# 07_-_OUTPUT.net
KiCad netlist of a schematic drawn in Altium Designer
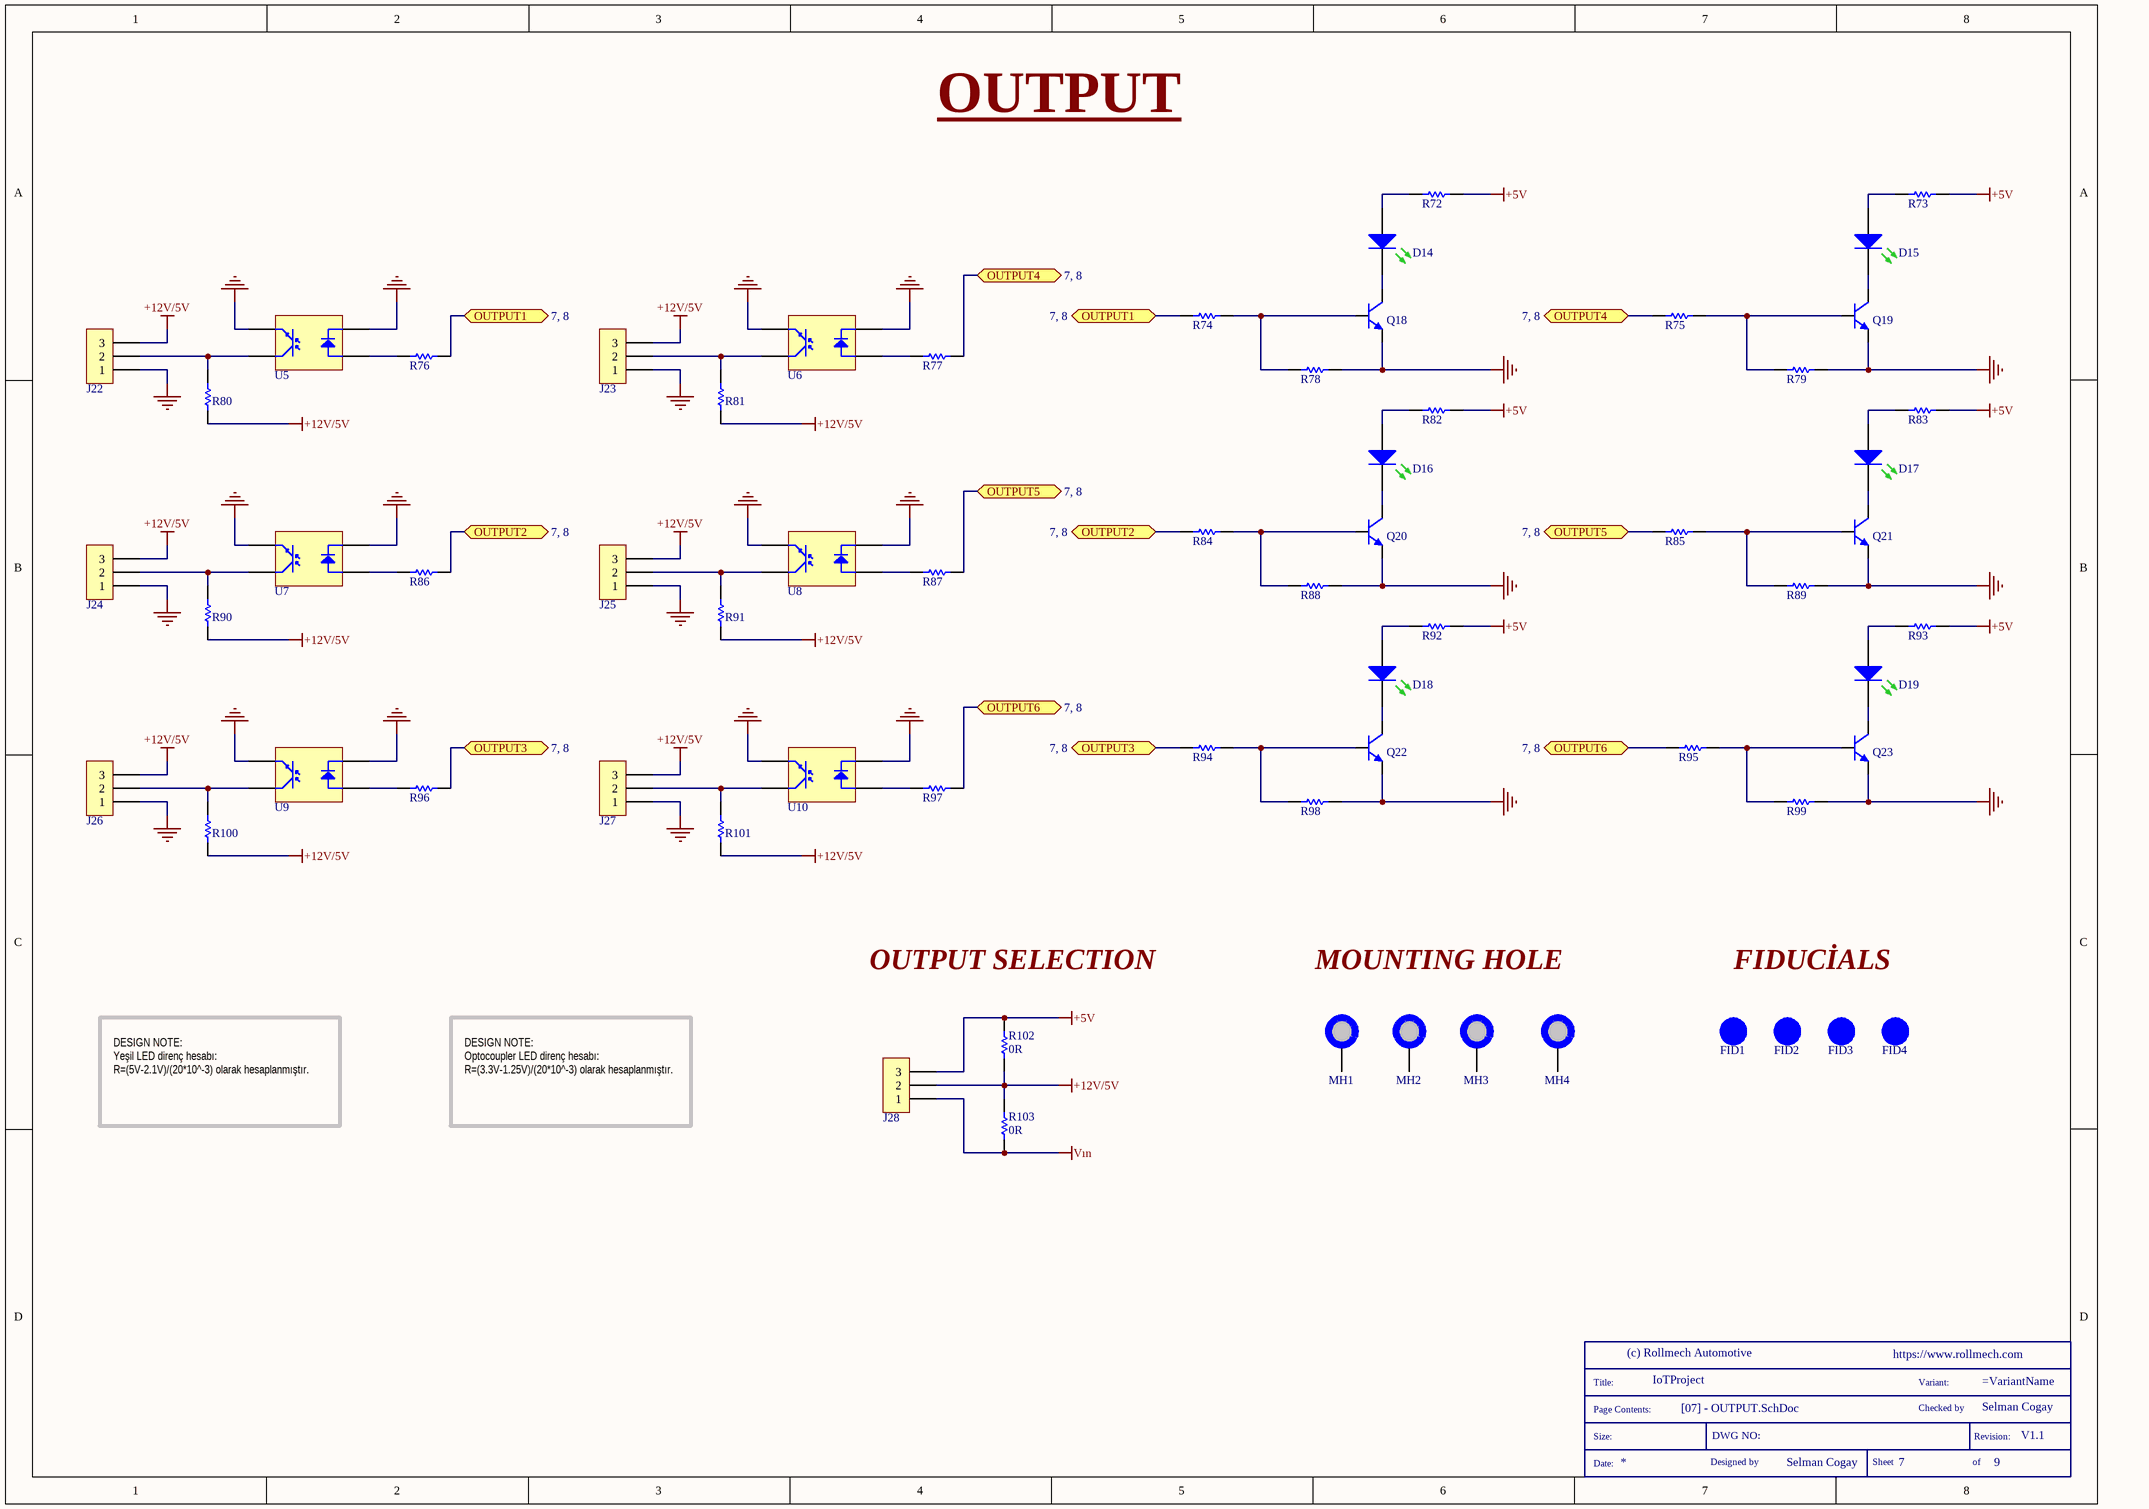
[diagram p0: [07] - OUTPUT.SchDoc]

(export (version "E")
  (design (tool "Eeschema 10.0.6"))
  (components
    (comp (ref "D14")
      (value "LED GREEN")
      (footprint "PLCC2")
      (description "LED TOPLED GREEN 562NM 2PLCC")
      (libsource (lib "Rollmech_Altium") (part "LP T67F-P1R2-35-1-20-R18-Z"))
    )
    (comp (ref "D15")
      (value "LED GREEN")
      (footprint "PLCC2")
      (description "LED TOPLED GREEN 562NM 2PLCC")
      (libsource (lib "Rollmech_Altium") (part "LP T67F-P1R2-35-1-20-R18-Z"))
    )
    (comp (ref "D16")
      (value "LED GREEN")
      (footprint "PLCC2")
      (description "LED TOPLED GREEN 562NM 2PLCC")
      (libsource (lib "Rollmech_Altium") (part "LP T67F-P1R2-35-1-20-R18-Z"))
    )
    (comp (ref "D17")
      (value "LED GREEN")
      (footprint "PLCC2")
      (description "LED TOPLED GREEN 562NM 2PLCC")
      (libsource (lib "Rollmech_Altium") (part "LP T67F-P1R2-35-1-20-R18-Z"))
    )
    (comp (ref "D18")
      (value "LED GREEN")
      (footprint "PLCC2")
      (description "LED TOPLED GREEN 562NM 2PLCC")
      (libsource (lib "Rollmech_Altium") (part "LP T67F-P1R2-35-1-20-R18-Z"))
    )
    (comp (ref "D19")
      (value "LED GREEN")
      (footprint "PLCC2")
      (description "LED TOPLED GREEN 562NM 2PLCC")
      (libsource (lib "Rollmech_Altium") (part "LP T67F-P1R2-35-1-20-R18-Z"))
    )
    (comp (ref "FID1")
      (value "FID_1MMC")
      (footprint "FID_40x120D")
      (description "Fiducial 40 mil diameter , 120 mil mask")
      (libsource (lib "Rollmech_Altium") (part "FID_1MMC"))
    )
    (comp (ref "FID2")
      (value "FID_1MMC")
      (footprint "FID_40x120D")
      (description "Fiducial 40 mil diameter , 120 mil mask")
      (libsource (lib "Rollmech_Altium") (part "FID_1MMC"))
    )
    (comp (ref "FID3")
      (value "FID_1MMC")
      (footprint "FID_40x120D")
      (description "Fiducial 40 mil diameter , 120 mil mask")
      (libsource (lib "Rollmech_Altium") (part "FID_1MMC"))
    )
    (comp (ref "FID4")
      (value "FID_1MMC")
      (footprint "FID_40x120D")
      (description "Fiducial 40 mil diameter , 120 mil mask")
      (libsource (lib "Rollmech_Altium") (part "FID_1MMC"))
    )
    (comp (ref "J22")
      (value "CONN 1X3 3MM")
      (footprint "CONN_MALE_1X3_3MM")
      (description "CONN MALE 1X3 3MM")
      (libsource (lib "Rollmech_Altium") (part "66200311122"))
    )
    (comp (ref "J23")
      (value "CONN 1X3 3MM")
      (footprint "CONN_MALE_1X3_3MM")
      (description "CONN MALE 1X3 3MM")
      (libsource (lib "Rollmech_Altium") (part "66200311122"))
    )
    (comp (ref "J24")
      (value "CONN 1X3 3MM")
      (footprint "CONN_MALE_1X3_3MM")
      (description "CONN MALE 1X3 3MM")
      (libsource (lib "Rollmech_Altium") (part "66200311122"))
    )
    (comp (ref "J25")
      (value "CONN 1X3 3MM")
      (footprint "CONN_MALE_1X3_3MM")
      (description "CONN MALE 1X3 3MM")
      (libsource (lib "Rollmech_Altium") (part "66200311122"))
    )
    (comp (ref "J26")
      (value "CONN 1X3 3MM")
      (footprint "CONN_MALE_1X3_3MM")
      (description "CONN MALE 1X3 3MM")
      (libsource (lib "Rollmech_Altium") (part "66200311122"))
    )
    (comp (ref "J27")
      (value "CONN 1X3 3MM")
      (footprint "CONN_MALE_1X3_3MM")
      (description "CONN MALE 1X3 3MM")
      (libsource (lib "Rollmech_Altium") (part "66200311122"))
    )
    (comp (ref "J28")
      (value "HDR_1X3_2.54")
      (footprint "HDR_MALE_1X3_2.54MM")
      (description "HDR MALE 1X3 2.54MM")
      (libsource (lib "Rollmech_Altium") (part "61300311121"))
    )
    (comp (ref "MH1")
      (value "MH_3mm")
      (footprint "MH_3MM")
      (description "Mounting Hole 3 mm")
      (libsource (lib "Rollmech_Altium") (part "Mounting Hole 3mm"))
    )
    (comp (ref "MH2")
      (value "MH_3mm")
      (footprint "MH_3MM")
      (description "Mounting Hole 3 mm")
      (libsource (lib "Rollmech_Altium") (part "Mounting Hole 3mm"))
    )
    (comp (ref "MH3")
      (value "MH_3mm")
      (footprint "MH_3MM")
      (description "Mounting Hole 3 mm")
      (libsource (lib "Rollmech_Altium") (part "Mounting Hole 3mm"))
    )
    (comp (ref "MH4")
      (value "MH_3mm")
      (footprint "MH_3MM")
      (description "Mounting Hole 3 mm")
      (libsource (lib "Rollmech_Altium") (part "Mounting Hole 3mm"))
    )
    (comp (ref "Q18")
      (value "NPN 0.6A")
      (footprint "SOT-23 (TO-236)")
      (description "TRANS NPN 40V 0.6A SMD SOT23-3")
      (libsource (lib "Rollmech_Altium") (part "MMBT2222A-7-F"))
    )
    (comp (ref "Q19")
      (value "NPN 0.6A")
      (footprint "SOT-23 (TO-236)")
      (description "TRANS NPN 40V 0.6A SMD SOT23-3")
      (libsource (lib "Rollmech_Altium") (part "MMBT2222A-7-F"))
    )
    (comp (ref "Q20")
      (value "NPN 0.6A")
      (footprint "SOT-23 (TO-236)")
      (description "TRANS NPN 40V 0.6A SMD SOT23-3")
      (libsource (lib "Rollmech_Altium") (part "MMBT2222A-7-F"))
    )
    (comp (ref "Q21")
      (value "NPN 0.6A")
      (footprint "SOT-23 (TO-236)")
      (description "TRANS NPN 40V 0.6A SMD SOT23-3")
      (libsource (lib "Rollmech_Altium") (part "MMBT2222A-7-F"))
    )
    (comp (ref "Q22")
      (value "NPN 0.6A")
      (footprint "SOT-23 (TO-236)")
      (description "TRANS NPN 40V 0.6A SMD SOT23-3")
      (libsource (lib "Rollmech_Altium") (part "MMBT2222A-7-F"))
    )
    (comp (ref "Q23")
      (value "NPN 0.6A")
      (footprint "SOT-23 (TO-236)")
      (description "TRANS NPN 40V 0.6A SMD SOT23-3")
      (libsource (lib "Rollmech_Altium") (part "MMBT2222A-7-F"))
    )
    (comp (ref "R72")
      (value "140 1/8W")
      (footprint "RES_0805")
      (description "RES SMD 140 OHM 1% 1/8W 0805")
      (libsource (lib "Rollmech_Altium") (part "ERJ-6ENF1400V"))
    )
    (comp (ref "R73")
      (value "140 1/8W")
      (footprint "RES_0805")
      (description "RES SMD 140 OHM 1% 1/8W 0805")
      (libsource (lib "Rollmech_Altium") (part "ERJ-6ENF1400V"))
    )
    (comp (ref "R74")
      (value "10K 1/8W")
      (footprint "RES_0805")
      (description "RES SMD 10K OHM 1% 1/8W 0805")
      (libsource (lib "Rollmech_Altium") (part "ERJ-6ENF1002V"))
    )
    (comp (ref "R75")
      (value "10K 1/8W")
      (footprint "RES_0805")
      (description "RES SMD 10K OHM 1% 1/8W 0805")
      (libsource (lib "Rollmech_Altium") (part "ERJ-6ENF1002V"))
    )
    (comp (ref "R76")
      (value "100 1/8W")
      (footprint "RES_0805")
      (description "RES SMD 100 OHM")
      (libsource (lib "Rollmech_Altium") (part "ERJ-6ENF1000V"))
    )
    (comp (ref "R77")
      (value "100 1/8W")
      (footprint "RES_0805")
      (description "RES SMD 100 OHM")
      (libsource (lib "Rollmech_Altium") (part "ERJ-6ENF1000V"))
    )
    (comp (ref "R78")
      (value "100K 1/4W")
      (footprint "RES_0603")
      (description "RES SMD 100K 5% 1/4W 0603")
      (libsource (lib "Rollmech_Altium") (part "ERJ-PA3J104V"))
    )
    (comp (ref "R79")
      (value "100K 1/4W")
      (footprint "RES_0603")
      (description "RES SMD 100K 5% 1/4W 0603")
      (libsource (lib "Rollmech_Altium") (part "ERJ-PA3J104V"))
    )
    (comp (ref "R80")
      (value "5.6k 1/8W")
      (footprint "RES_0805")
      (description "RES SMD 5.6K OHM 1% 1/8W 0805")
      (libsource (lib "Rollmech_Altium") (part "ERJ-6ENF5601V"))
    )
    (comp (ref "R81")
      (value "5.6k 1/8W")
      (footprint "RES_0805")
      (description "RES SMD 5.6K OHM 1% 1/8W 0805")
      (libsource (lib "Rollmech_Altium") (part "ERJ-6ENF5601V"))
    )
    (comp (ref "R82")
      (value "140 1/8W")
      (footprint "RES_0805")
      (description "RES SMD 140 OHM 1% 1/8W 0805")
      (libsource (lib "Rollmech_Altium") (part "ERJ-6ENF1400V"))
    )
    (comp (ref "R83")
      (value "140 1/8W")
      (footprint "RES_0805")
      (description "RES SMD 140 OHM 1% 1/8W 0805")
      (libsource (lib "Rollmech_Altium") (part "ERJ-6ENF1400V"))
    )
    (comp (ref "R84")
      (value "10K 1/8W")
      (footprint "RES_0805")
      (description "RES SMD 10K OHM 1% 1/8W 0805")
      (libsource (lib "Rollmech_Altium") (part "ERJ-6ENF1002V"))
    )
    (comp (ref "R85")
      (value "10K 1/8W")
      (footprint "RES_0805")
      (description "RES SMD 10K OHM 1% 1/8W 0805")
      (libsource (lib "Rollmech_Altium") (part "ERJ-6ENF1002V"))
    )
    (comp (ref "R86")
      (value "100 1/8W")
      (footprint "RES_0805")
      (description "RES SMD 100 OHM")
      (libsource (lib "Rollmech_Altium") (part "ERJ-6ENF1000V"))
    )
    (comp (ref "R87")
      (value "100 1/8W")
      (footprint "RES_0805")
      (description "RES SMD 100 OHM")
      (libsource (lib "Rollmech_Altium") (part "ERJ-6ENF1000V"))
    )
    (comp (ref "R88")
      (value "100K 1/4W")
      (footprint "RES_0603")
      (description "RES SMD 100K 5% 1/4W 0603")
      (libsource (lib "Rollmech_Altium") (part "ERJ-PA3J104V"))
    )
    (comp (ref "R89")
      (value "100K 1/4W")
      (footprint "RES_0603")
      (description "RES SMD 100K 5% 1/4W 0603")
      (libsource (lib "Rollmech_Altium") (part "ERJ-PA3J104V"))
    )
    (comp (ref "R90")
      (value "5.6k 1/8W")
      (footprint "RES_0805")
      (description "RES SMD 5.6K OHM 1% 1/8W 0805")
      (libsource (lib "Rollmech_Altium") (part "ERJ-6ENF5601V"))
    )
    (comp (ref "R91")
      (value "5.6k 1/8W")
      (footprint "RES_0805")
      (description "RES SMD 5.6K OHM 1% 1/8W 0805")
      (libsource (lib "Rollmech_Altium") (part "ERJ-6ENF5601V"))
    )
    (comp (ref "R92")
      (value "140 1/8W")
      (footprint "RES_0805")
      (description "RES SMD 140 OHM 1% 1/8W 0805")
      (libsource (lib "Rollmech_Altium") (part "ERJ-6ENF1400V"))
    )
    (comp (ref "R93")
      (value "140 1/8W")
      (footprint "RES_0805")
      (description "RES SMD 140 OHM 1% 1/8W 0805")
      (libsource (lib "Rollmech_Altium") (part "ERJ-6ENF1400V"))
    )
    (comp (ref "R94")
      (value "10K 1/8W")
      (footprint "RES_0805")
      (description "RES SMD 10K OHM 1% 1/8W 0805")
      (libsource (lib "Rollmech_Altium") (part "ERJ-6ENF1002V"))
    )
    (comp (ref "R95")
      (value "10K 1/8W")
      (footprint "RES_0805")
      (description "RES SMD 10K OHM 1% 1/8W 0805")
      (libsource (lib "Rollmech_Altium") (part "ERJ-6ENF1002V"))
    )
    (comp (ref "R96")
      (value "100 1/8W")
      (footprint "RES_0805")
      (description "RES SMD 100 OHM")
      (libsource (lib "Rollmech_Altium") (part "ERJ-6ENF1000V"))
    )
    (comp (ref "R97")
      (value "100 1/8W")
      (footprint "RES_0805")
      (description "RES SMD 100 OHM")
      (libsource (lib "Rollmech_Altium") (part "ERJ-6ENF1000V"))
    )
    (comp (ref "R98")
      (value "100K 1/4W")
      (footprint "RES_0603")
      (description "RES SMD 100K 5% 1/4W 0603")
      (libsource (lib "Rollmech_Altium") (part "ERJ-PA3J104V"))
    )
    (comp (ref "R99")
      (value "100K 1/4W")
      (footprint "RES_0603")
      (description "RES SMD 100K 5% 1/4W 0603")
      (libsource (lib "Rollmech_Altium") (part "ERJ-PA3J104V"))
    )
    (comp (ref "R100")
      (value "5.6k 1/8W")
      (footprint "RES_0805")
      (description "RES SMD 5.6K OHM 1% 1/8W 0805")
      (libsource (lib "Rollmech_Altium") (part "ERJ-6ENF5601V"))
    )
    (comp (ref "R101")
      (value "5.6k 1/8W")
      (footprint "RES_0805")
      (description "RES SMD 5.6K OHM 1% 1/8W 0805")
      (libsource (lib "Rollmech_Altium") (part "ERJ-6ENF5601V"))
    )
    (comp (ref "R102")
      (value "0R")
      (footprint "R0805")
      (description "RES SMD 0 OHM JUMPER 1/8W 0805")
      (libsource (lib "SN65HVD2xx-CAN-Module-V1I1") (part "CRCW08050000Z0EA"))
    )
    (comp (ref "R103")
      (value "0R")
      (footprint "R0805")
      (description "RES SMD 0 OHM JUMPER 1/8W 0805")
      (libsource (lib "SN65HVD2xx-CAN-Module-V1I1") (part "CRCW08050000Z0EA"))
    )
    (comp (ref "U5")
      (value "NPN 3.75KV")
      (footprint "SOIC-6")
      (description "OPTOISO 3.75KV TRANS")
      (libsource (lib "Rollmech_Altium") (part "TLP2301(TPL,E"))
    )
    (comp (ref "U6")
      (value "NPN 3.75KV")
      (footprint "SOIC-6")
      (description "OPTOISO 3.75KV TRANS")
      (libsource (lib "Rollmech_Altium") (part "TLP2301(TPL,E"))
    )
    (comp (ref "U7")
      (value "NPN 3.75KV")
      (footprint "SOIC-6")
      (description "OPTOISO 3.75KV TRANS")
      (libsource (lib "Rollmech_Altium") (part "TLP2301(TPL,E"))
    )
    (comp (ref "U8")
      (value "NPN 3.75KV")
      (footprint "SOIC-6")
      (description "OPTOISO 3.75KV TRANS")
      (libsource (lib "Rollmech_Altium") (part "TLP2301(TPL,E"))
    )
    (comp (ref "U9")
      (value "NPN 3.75KV")
      (footprint "SOIC-6")
      (description "OPTOISO 3.75KV TRANS")
      (libsource (lib "Rollmech_Altium") (part "TLP2301(TPL,E"))
    )
    (comp (ref "U10")
      (value "NPN 3.75KV")
      (footprint "SOIC-6")
      (description "OPTOISO 3.75KV TRANS")
      (libsource (lib "Rollmech_Altium") (part "TLP2301(TPL,E"))
    )
  )
  (nets
    (net (code "1") (name "+5V") (class "Default")
      (node (ref "J28") (pin "3") (pinfunction "3_3") (pintype "passive"))
      (node (ref "R102") (pin "1") (pinfunction "1_1") (pintype "passive"))
      (node (ref "R72") (pin "2") (pinfunction "2_2") (pintype "passive"))
      (node (ref "R73") (pin "2") (pinfunction "2_2") (pintype "passive"))
      (node (ref "R82") (pin "2") (pinfunction "2_2") (pintype "passive"))
      (node (ref "R83") (pin "2") (pinfunction "2_2") (pintype "passive"))
      (node (ref "R92") (pin "2") (pinfunction "2_2") (pintype "passive"))
      (node (ref "R93") (pin "2") (pinfunction "2_2") (pintype "passive"))
    )
    (net (code "2") (name "+12V{slash}5V") (class "Default")
      (node (ref "J22") (pin "3") (pinfunction "3_3") (pintype "passive"))
      (node (ref "J23") (pin "3") (pinfunction "3_3") (pintype "passive"))
      (node (ref "J24") (pin "3") (pinfunction "3_3") (pintype "passive"))
      (node (ref "J25") (pin "3") (pinfunction "3_3") (pintype "passive"))
      (node (ref "J26") (pin "3") (pinfunction "3_3") (pintype "passive"))
      (node (ref "J27") (pin "3") (pinfunction "3_3") (pintype "passive"))
      (node (ref "J28") (pin "2") (pinfunction "2_2") (pintype "passive"))
      (node (ref "R100") (pin "1") (pinfunction "1_1") (pintype "passive"))
      (node (ref "R101") (pin "1") (pinfunction "1_1") (pintype "passive"))
      (node (ref "R102") (pin "2") (pinfunction "2_2") (pintype "passive"))
      (node (ref "R103") (pin "1") (pinfunction "1_1") (pintype "passive"))
      (node (ref "R80") (pin "1") (pinfunction "1_1") (pintype "passive"))
      (node (ref "R81") (pin "1") (pinfunction "1_1") (pintype "passive"))
      (node (ref "R90") (pin "1") (pinfunction "1_1") (pintype "passive"))
      (node (ref "R91") (pin "1") (pinfunction "1_1") (pintype "passive"))
    )
    (net (code "3") (name "/OUTPUT1") (class "Default")
      (node (ref "R74") (pin "1") (pinfunction "1_1") (pintype "passive"))
      (node (ref "R76") (pin "2") (pinfunction "2_2") (pintype "passive"))
    )
    (net (code "4") (name "/OUTPUT2") (class "Default")
      (node (ref "R84") (pin "1") (pinfunction "1_1") (pintype "passive"))
      (node (ref "R86") (pin "2") (pinfunction "2_2") (pintype "passive"))
    )
    (net (code "5") (name "/OUTPUT3") (class "Default")
      (node (ref "R94") (pin "1") (pinfunction "1_1") (pintype "passive"))
      (node (ref "R96") (pin "2") (pinfunction "2_2") (pintype "passive"))
    )
    (net (code "6") (name "/OUTPUT4") (class "Default")
      (node (ref "R75") (pin "1") (pinfunction "1_1") (pintype "passive"))
      (node (ref "R77") (pin "2") (pinfunction "2_2") (pintype "passive"))
    )
    (net (code "7") (name "/OUTPUT5") (class "Default")
      (node (ref "R85") (pin "1") (pinfunction "1_1") (pintype "passive"))
      (node (ref "R87") (pin "2") (pinfunction "2_2") (pintype "passive"))
    )
    (net (code "8") (name "/OUTPUT6") (class "Default")
      (node (ref "R95") (pin "1") (pinfunction "1_1") (pintype "passive"))
      (node (ref "R97") (pin "2") (pinfunction "2_2") (pintype "passive"))
    )
    (net (code "9") (name "GND") (class "Default")
      (node (ref "J22") (pin "1") (pinfunction "1_1") (pintype "passive"))
      (node (ref "J23") (pin "1") (pinfunction "1_1") (pintype "passive"))
      (node (ref "J24") (pin "1") (pinfunction "1_1") (pintype "passive"))
      (node (ref "J25") (pin "1") (pinfunction "1_1") (pintype "passive"))
      (node (ref "J26") (pin "1") (pinfunction "1_1") (pintype "passive"))
      (node (ref "J27") (pin "1") (pinfunction "1_1") (pintype "passive"))
      (node (ref "Q18") (pin "3") (pinfunction "E_3") (pintype "passive"))
      (node (ref "Q19") (pin "3") (pinfunction "E_3") (pintype "passive"))
      (node (ref "Q20") (pin "3") (pinfunction "E_3") (pintype "passive"))
      (node (ref "Q21") (pin "3") (pinfunction "E_3") (pintype "passive"))
      (node (ref "Q22") (pin "3") (pinfunction "E_3") (pintype "passive"))
      (node (ref "Q23") (pin "3") (pinfunction "E_3") (pintype "passive"))
      (node (ref "R78") (pin "2") (pinfunction "2_2") (pintype "passive"))
      (node (ref "R79") (pin "2") (pinfunction "2_2") (pintype "passive"))
      (node (ref "R88") (pin "2") (pinfunction "2_2") (pintype "passive"))
      (node (ref "R89") (pin "2") (pinfunction "2_2") (pintype "passive"))
      (node (ref "R98") (pin "2") (pinfunction "2_2") (pintype "passive"))
      (node (ref "R99") (pin "2") (pinfunction "2_2") (pintype "passive"))
      (node (ref "U10") (pin "3") (pinfunction "K_3") (pintype "passive"))
      (node (ref "U10") (pin "4") (pinfunction "Emit_4") (pintype "passive"))
      (node (ref "U5") (pin "3") (pinfunction "K_3") (pintype "passive"))
      (node (ref "U5") (pin "4") (pinfunction "Emit_4") (pintype "passive"))
      (node (ref "U6") (pin "3") (pinfunction "K_3") (pintype "passive"))
      (node (ref "U6") (pin "4") (pinfunction "Emit_4") (pintype "passive"))
      (node (ref "U7") (pin "3") (pinfunction "K_3") (pintype "passive"))
      (node (ref "U7") (pin "4") (pinfunction "Emit_4") (pintype "passive"))
      (node (ref "U8") (pin "3") (pinfunction "K_3") (pintype "passive"))
      (node (ref "U8") (pin "4") (pinfunction "Emit_4") (pintype "passive"))
      (node (ref "U9") (pin "3") (pinfunction "K_3") (pintype "passive"))
      (node (ref "U9") (pin "4") (pinfunction "Emit_4") (pintype "passive"))
    )
    (net (code "10") (name "Net-(D14-A)") (class "Default")
      (node (ref "D14") (pin "1") (pinfunction "A_1") (pintype "passive"))
      (node (ref "R72") (pin "1") (pinfunction "1_1") (pintype "passive"))
    )
    (net (code "11") (name "Net-(D14-K)") (class "Default")
      (node (ref "D14") (pin "2") (pinfunction "K_2") (pintype "passive"))
      (node (ref "Q18") (pin "1") (pinfunction "C_1") (pintype "passive"))
    )
    (net (code "12") (name "Net-(D15-A)") (class "Default")
      (node (ref "D15") (pin "1") (pinfunction "A_1") (pintype "passive"))
      (node (ref "R73") (pin "1") (pinfunction "1_1") (pintype "passive"))
    )
    (net (code "13") (name "Net-(D15-K)") (class "Default")
      (node (ref "D15") (pin "2") (pinfunction "K_2") (pintype "passive"))
      (node (ref "Q19") (pin "1") (pinfunction "C_1") (pintype "passive"))
    )
    (net (code "14") (name "Net-(D16-A)") (class "Default")
      (node (ref "D16") (pin "1") (pinfunction "A_1") (pintype "passive"))
      (node (ref "R82") (pin "1") (pinfunction "1_1") (pintype "passive"))
    )
    (net (code "15") (name "Net-(D16-K)") (class "Default")
      (node (ref "D16") (pin "2") (pinfunction "K_2") (pintype "passive"))
      (node (ref "Q20") (pin "1") (pinfunction "C_1") (pintype "passive"))
    )
    (net (code "16") (name "Net-(D17-A)") (class "Default")
      (node (ref "D17") (pin "1") (pinfunction "A_1") (pintype "passive"))
      (node (ref "R83") (pin "1") (pinfunction "1_1") (pintype "passive"))
    )
    (net (code "17") (name "Net-(D17-K)") (class "Default")
      (node (ref "D17") (pin "2") (pinfunction "K_2") (pintype "passive"))
      (node (ref "Q21") (pin "1") (pinfunction "C_1") (pintype "passive"))
    )
    (net (code "18") (name "Net-(D18-A)") (class "Default")
      (node (ref "D18") (pin "1") (pinfunction "A_1") (pintype "passive"))
      (node (ref "R92") (pin "1") (pinfunction "1_1") (pintype "passive"))
    )
    (net (code "19") (name "Net-(D18-K)") (class "Default")
      (node (ref "D18") (pin "2") (pinfunction "K_2") (pintype "passive"))
      (node (ref "Q22") (pin "1") (pinfunction "C_1") (pintype "passive"))
    )
    (net (code "20") (name "Net-(D19-A)") (class "Default")
      (node (ref "D19") (pin "1") (pinfunction "A_1") (pintype "passive"))
      (node (ref "R93") (pin "1") (pinfunction "1_1") (pintype "passive"))
    )
    (net (code "21") (name "Net-(D19-K)") (class "Default")
      (node (ref "D19") (pin "2") (pinfunction "K_2") (pintype "passive"))
      (node (ref "Q23") (pin "1") (pinfunction "C_1") (pintype "passive"))
    )
    (net (code "22") (name "Net-(Q18-B)") (class "Default")
      (node (ref "Q18") (pin "2") (pinfunction "B_2") (pintype "passive"))
      (node (ref "R74") (pin "2") (pinfunction "2_2") (pintype "passive"))
      (node (ref "R78") (pin "1") (pinfunction "1_1") (pintype "passive"))
    )
    (net (code "23") (name "Net-(Q19-B)") (class "Default")
      (node (ref "Q19") (pin "2") (pinfunction "B_2") (pintype "passive"))
      (node (ref "R75") (pin "2") (pinfunction "2_2") (pintype "passive"))
      (node (ref "R79") (pin "1") (pinfunction "1_1") (pintype "passive"))
    )
    (net (code "24") (name "Net-(Q20-B)") (class "Default")
      (node (ref "Q20") (pin "2") (pinfunction "B_2") (pintype "passive"))
      (node (ref "R84") (pin "2") (pinfunction "2_2") (pintype "passive"))
      (node (ref "R88") (pin "1") (pinfunction "1_1") (pintype "passive"))
    )
    (net (code "25") (name "Net-(Q21-B)") (class "Default")
      (node (ref "Q21") (pin "2") (pinfunction "B_2") (pintype "passive"))
      (node (ref "R85") (pin "2") (pinfunction "2_2") (pintype "passive"))
      (node (ref "R89") (pin "1") (pinfunction "1_1") (pintype "passive"))
    )
    (net (code "26") (name "Net-(Q22-B)") (class "Default")
      (node (ref "Q22") (pin "2") (pinfunction "B_2") (pintype "passive"))
      (node (ref "R94") (pin "2") (pinfunction "2_2") (pintype "passive"))
      (node (ref "R98") (pin "1") (pinfunction "1_1") (pintype "passive"))
    )
    (net (code "27") (name "Net-(Q23-B)") (class "Default")
      (node (ref "Q23") (pin "2") (pinfunction "B_2") (pintype "passive"))
      (node (ref "R95") (pin "2") (pinfunction "2_2") (pintype "passive"))
      (node (ref "R99") (pin "1") (pinfunction "1_1") (pintype "passive"))
    )
    (net (code "28") (name "Net-(U5-A)") (class "Default")
      (node (ref "R76") (pin "1") (pinfunction "1_1") (pintype "passive"))
      (node (ref "U5") (pin "1") (pinfunction "A_1") (pintype "passive"))
    )
    (net (code "29") (name "Net-(U5-Coll)") (class "Default")
      (node (ref "J22") (pin "2") (pinfunction "2_2") (pintype "passive"))
      (node (ref "R80") (pin "2") (pinfunction "2_2") (pintype "passive"))
      (node (ref "U5") (pin "6") (pinfunction "Coll_6") (pintype "passive"))
    )
    (net (code "30") (name "Net-(U6-A)") (class "Default")
      (node (ref "R77") (pin "1") (pinfunction "1_1") (pintype "passive"))
      (node (ref "U6") (pin "1") (pinfunction "A_1") (pintype "passive"))
    )
    (net (code "31") (name "Net-(U6-Coll)") (class "Default")
      (node (ref "J23") (pin "2") (pinfunction "2_2") (pintype "passive"))
      (node (ref "R81") (pin "2") (pinfunction "2_2") (pintype "passive"))
      (node (ref "U6") (pin "6") (pinfunction "Coll_6") (pintype "passive"))
    )
    (net (code "32") (name "Net-(U7-A)") (class "Default")
      (node (ref "R86") (pin "1") (pinfunction "1_1") (pintype "passive"))
      (node (ref "U7") (pin "1") (pinfunction "A_1") (pintype "passive"))
    )
    (net (code "33") (name "Net-(U7-Coll)") (class "Default")
      (node (ref "J24") (pin "2") (pinfunction "2_2") (pintype "passive"))
      (node (ref "R90") (pin "2") (pinfunction "2_2") (pintype "passive"))
      (node (ref "U7") (pin "6") (pinfunction "Coll_6") (pintype "passive"))
    )
    (net (code "34") (name "Net-(U8-A)") (class "Default")
      (node (ref "R87") (pin "1") (pinfunction "1_1") (pintype "passive"))
      (node (ref "U8") (pin "1") (pinfunction "A_1") (pintype "passive"))
    )
    (net (code "35") (name "Net-(U8-Coll)") (class "Default")
      (node (ref "J25") (pin "2") (pinfunction "2_2") (pintype "passive"))
      (node (ref "R91") (pin "2") (pinfunction "2_2") (pintype "passive"))
      (node (ref "U8") (pin "6") (pinfunction "Coll_6") (pintype "passive"))
    )
    (net (code "36") (name "Net-(U9-A)") (class "Default")
      (node (ref "R96") (pin "1") (pinfunction "1_1") (pintype "passive"))
      (node (ref "U9") (pin "1") (pinfunction "A_1") (pintype "passive"))
    )
    (net (code "37") (name "Net-(U9-Coll)") (class "Default")
      (node (ref "J26") (pin "2") (pinfunction "2_2") (pintype "passive"))
      (node (ref "R100") (pin "2") (pinfunction "2_2") (pintype "passive"))
      (node (ref "U9") (pin "6") (pinfunction "Coll_6") (pintype "passive"))
    )
    (net (code "38") (name "Net-(U10-A)") (class "Default")
      (node (ref "R97") (pin "1") (pinfunction "1_1") (pintype "passive"))
      (node (ref "U10") (pin "1") (pinfunction "A_1") (pintype "passive"))
    )
    (net (code "39") (name "Net-(U10-Coll)") (class "Default")
      (node (ref "J27") (pin "2") (pinfunction "2_2") (pintype "passive"))
      (node (ref "R101") (pin "2") (pinfunction "2_2") (pintype "passive"))
      (node (ref "U10") (pin "6") (pinfunction "Coll_6") (pintype "passive"))
    )
    (net (code "40") (name "Vın") (class "Default")
      (node (ref "J28") (pin "1") (pinfunction "1_1") (pintype "passive"))
      (node (ref "R103") (pin "2") (pinfunction "2_2") (pintype "passive"))
    )
    (net (code "41") (name "unconnected-(MH1-Pad1)") (class "Default")
      (node (ref "MH1") (pin "1") (pinfunction "1_1") (pintype "passive"))
    )
    (net (code "42") (name "unconnected-(MH2-Pad1)") (class "Default")
      (node (ref "MH2") (pin "1") (pinfunction "1_1") (pintype "passive"))
    )
    (net (code "43") (name "unconnected-(MH3-Pad1)") (class "Default")
      (node (ref "MH3") (pin "1") (pinfunction "1_1") (pintype "passive"))
    )
    (net (code "44") (name "unconnected-(MH4-Pad1)") (class "Default")
      (node (ref "MH4") (pin "1") (pinfunction "1_1") (pintype "passive"))
    )
  )
)
